# LED_blinking.net
KiCad netlist of a schematic drawn in EasyEDA
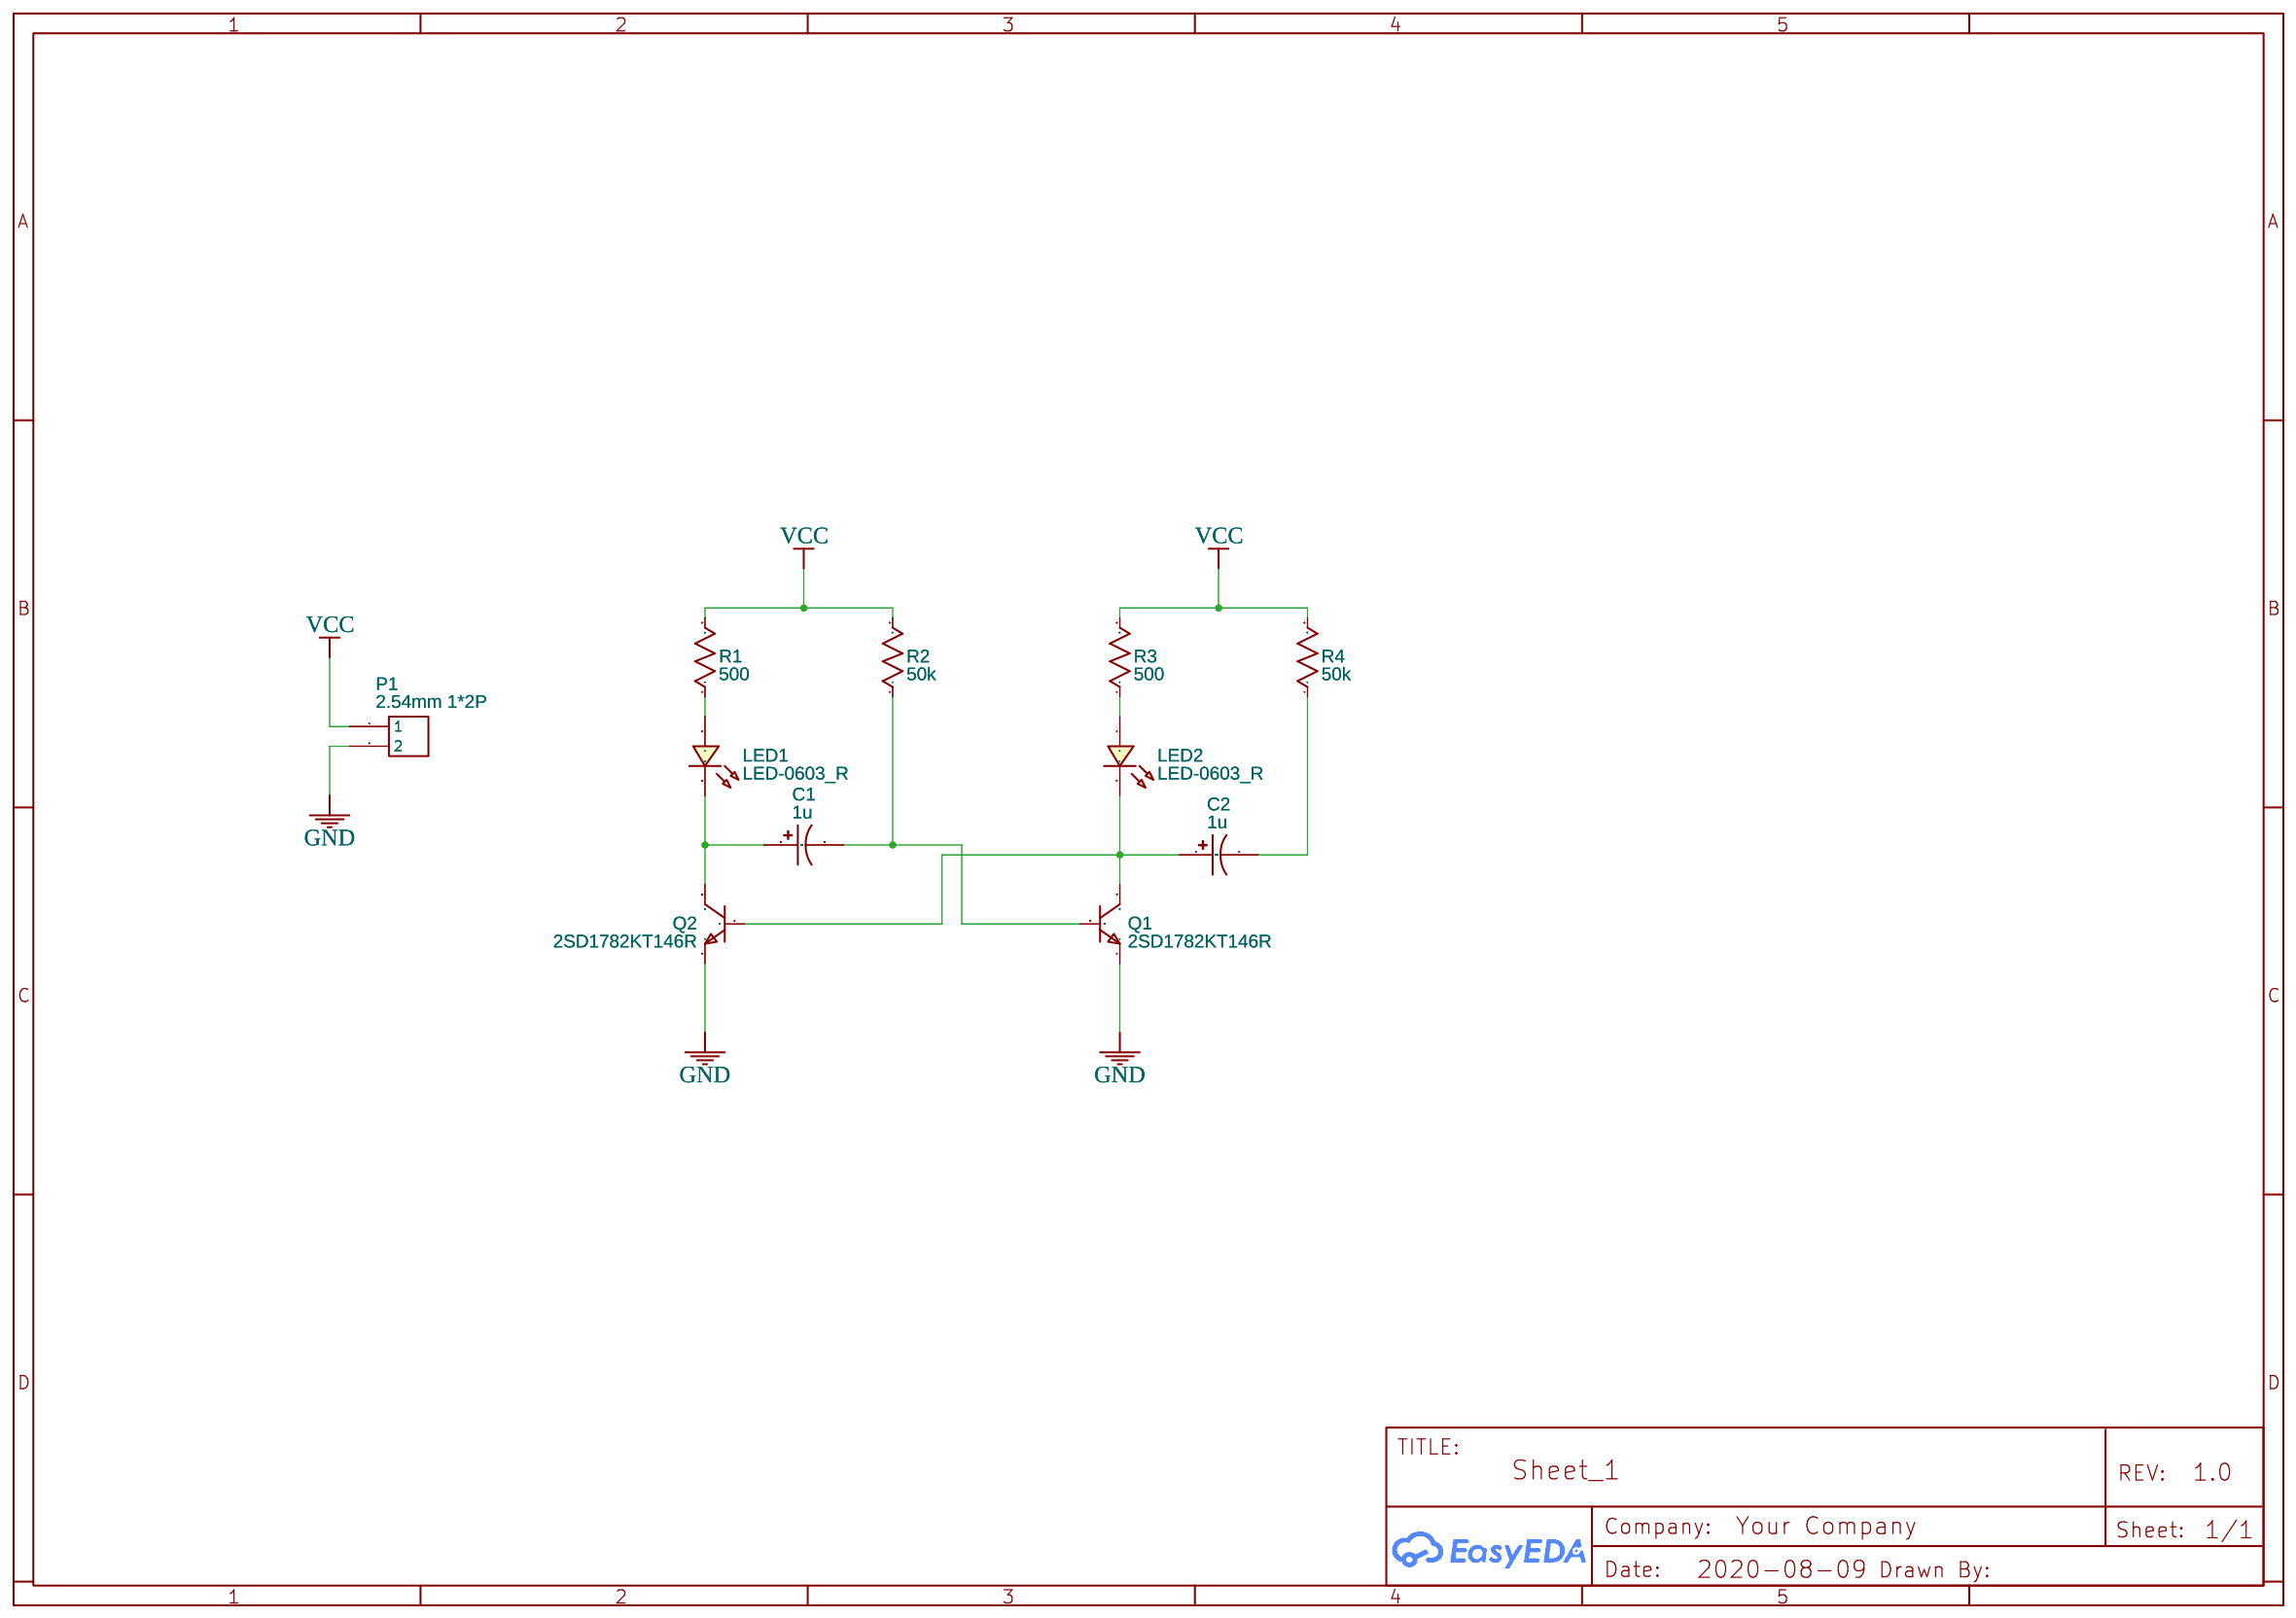
[diagram p0: schematic sheet]

(export (version "E")
  (design (tool "Eeschema 10.0.6"))
  (components
    (comp (ref "C1") (value "1u") (libsource (lib "") (part "C_Tan_SMD_A_US")))
    (comp (ref "C2") (value "1u") (libsource (lib "") (part "C_Tan_SMD_A_US")))
    (comp (ref "LED1")
      (value "LED-0603_R")
      (fields
        (field (name "BOM_Manufacturer Part") "19-217/R6C-AL1M2VY/3T")
        (field (name "BOM_Supplier Part") "C72044")
      )
      (libsource (lib "") (part "LED-0603_R"))
    )
    (comp (ref "LED2")
      (value "LED-0603_R")
      (fields
        (field (name "BOM_Manufacturer Part") "19-217/R6C-AL1M2VY/3T")
        (field (name "BOM_Supplier Part") "C72044")
      )
      (libsource (lib "") (part "LED-0603_R"))
    )
    (comp (ref "P1")
      (value "2.54mm 1*2P")
      (fields (field (name "BOM_Supplier Part") "C36717"))
      (libsource (lib "") (part "2.54mm 1*2P"))
    )
    (comp (ref "Q1")
      (value "2SD1782KT146R")
      (fields (field (name "BOM_Supplier Part") "C86593"))
      (libsource (lib "") (part "2SD1782KT146R_1"))
    )
    (comp (ref "Q2")
      (value "2SD1782KT146R")
      (fields (field (name "BOM_Supplier Part") "C86593"))
      (libsource (lib "") (part "2SD1782KT146R"))
    )
    (comp (ref "R1") (value "500") (libsource (lib "") (part "R_0603_US")))
    (comp (ref "R2") (value "50k") (libsource (lib "") (part "R_0603_US")))
    (comp (ref "R3") (value "500") (libsource (lib "") (part "R_0603_US")))
    (comp (ref "R4") (value "50k") (libsource (lib "") (part "R_0603_US")))
  )
  (nets
    (net (code "1") (name "GND") (class "Default")
      (node (ref "P1") (pin "2") (pinfunction "2_2") (pintype "input"))
      (node (ref "Q1") (pin "1") (pinfunction "E_1") (pintype "unspecified"))
      (node (ref "Q2") (pin "1") (pinfunction "E_1") (pintype "unspecified"))
    )
    (net (code "2") (name "Net-(C2-Pad2)") (class "Default")
      (node (ref "C2") (pin "2") (pinfunction "2_2") (pintype "unspecified"))
      (node (ref "R4") (pin "1") (pinfunction "1_1") (pintype "unspecified"))
    )
    (net (code "3") (name "Net-(LED1-Pad1)") (class "Default")
      (node (ref "LED1") (pin "1") (pinfunction "1_1") (pintype "unspecified"))
      (node (ref "R1") (pin "1") (pinfunction "1_1") (pintype "unspecified"))
    )
    (net (code "4") (name "Net-(LED2-Pad1)") (class "Default")
      (node (ref "LED2") (pin "1") (pinfunction "1_1") (pintype "unspecified"))
      (node (ref "R3") (pin "1") (pinfunction "1_1") (pintype "unspecified"))
    )
    (net (code "5") (name "Net-(Q1-B)") (class "Default")
      (node (ref "C1") (pin "2") (pinfunction "2_2") (pintype "unspecified"))
      (node (ref "Q1") (pin "2") (pinfunction "B_2") (pintype "unspecified"))
      (node (ref "R2") (pin "1") (pinfunction "1_1") (pintype "unspecified"))
    )
    (net (code "6") (name "Net-(Q1-C)") (class "Default")
      (node (ref "C2") (pin "1") (pinfunction "1_1") (pintype "unspecified"))
      (node (ref "LED2") (pin "2") (pinfunction "2_2") (pintype "unspecified"))
      (node (ref "Q1") (pin "3") (pinfunction "C_3") (pintype "unspecified"))
      (node (ref "Q2") (pin "2") (pinfunction "B_2") (pintype "unspecified"))
    )
    (net (code "7") (name "Net-(Q2-C)") (class "Default")
      (node (ref "C1") (pin "1") (pinfunction "1_1") (pintype "unspecified"))
      (node (ref "LED1") (pin "2") (pinfunction "2_2") (pintype "unspecified"))
      (node (ref "Q2") (pin "3") (pinfunction "C_3") (pintype "unspecified"))
    )
    (net (code "8") (name "VCC") (class "Default")
      (node (ref "P1") (pin "1") (pinfunction "1_1") (pintype "input"))
      (node (ref "R1") (pin "2") (pinfunction "2_2") (pintype "unspecified"))
      (node (ref "R2") (pin "2") (pinfunction "2_2") (pintype "unspecified"))
      (node (ref "R3") (pin "2") (pinfunction "2_2") (pintype "unspecified"))
      (node (ref "R4") (pin "2") (pinfunction "2_2") (pintype "unspecified"))
    )
  )
)
